# mSD-Shield_v10.net
KiCad netlist of a schematic drawn in EAGLE
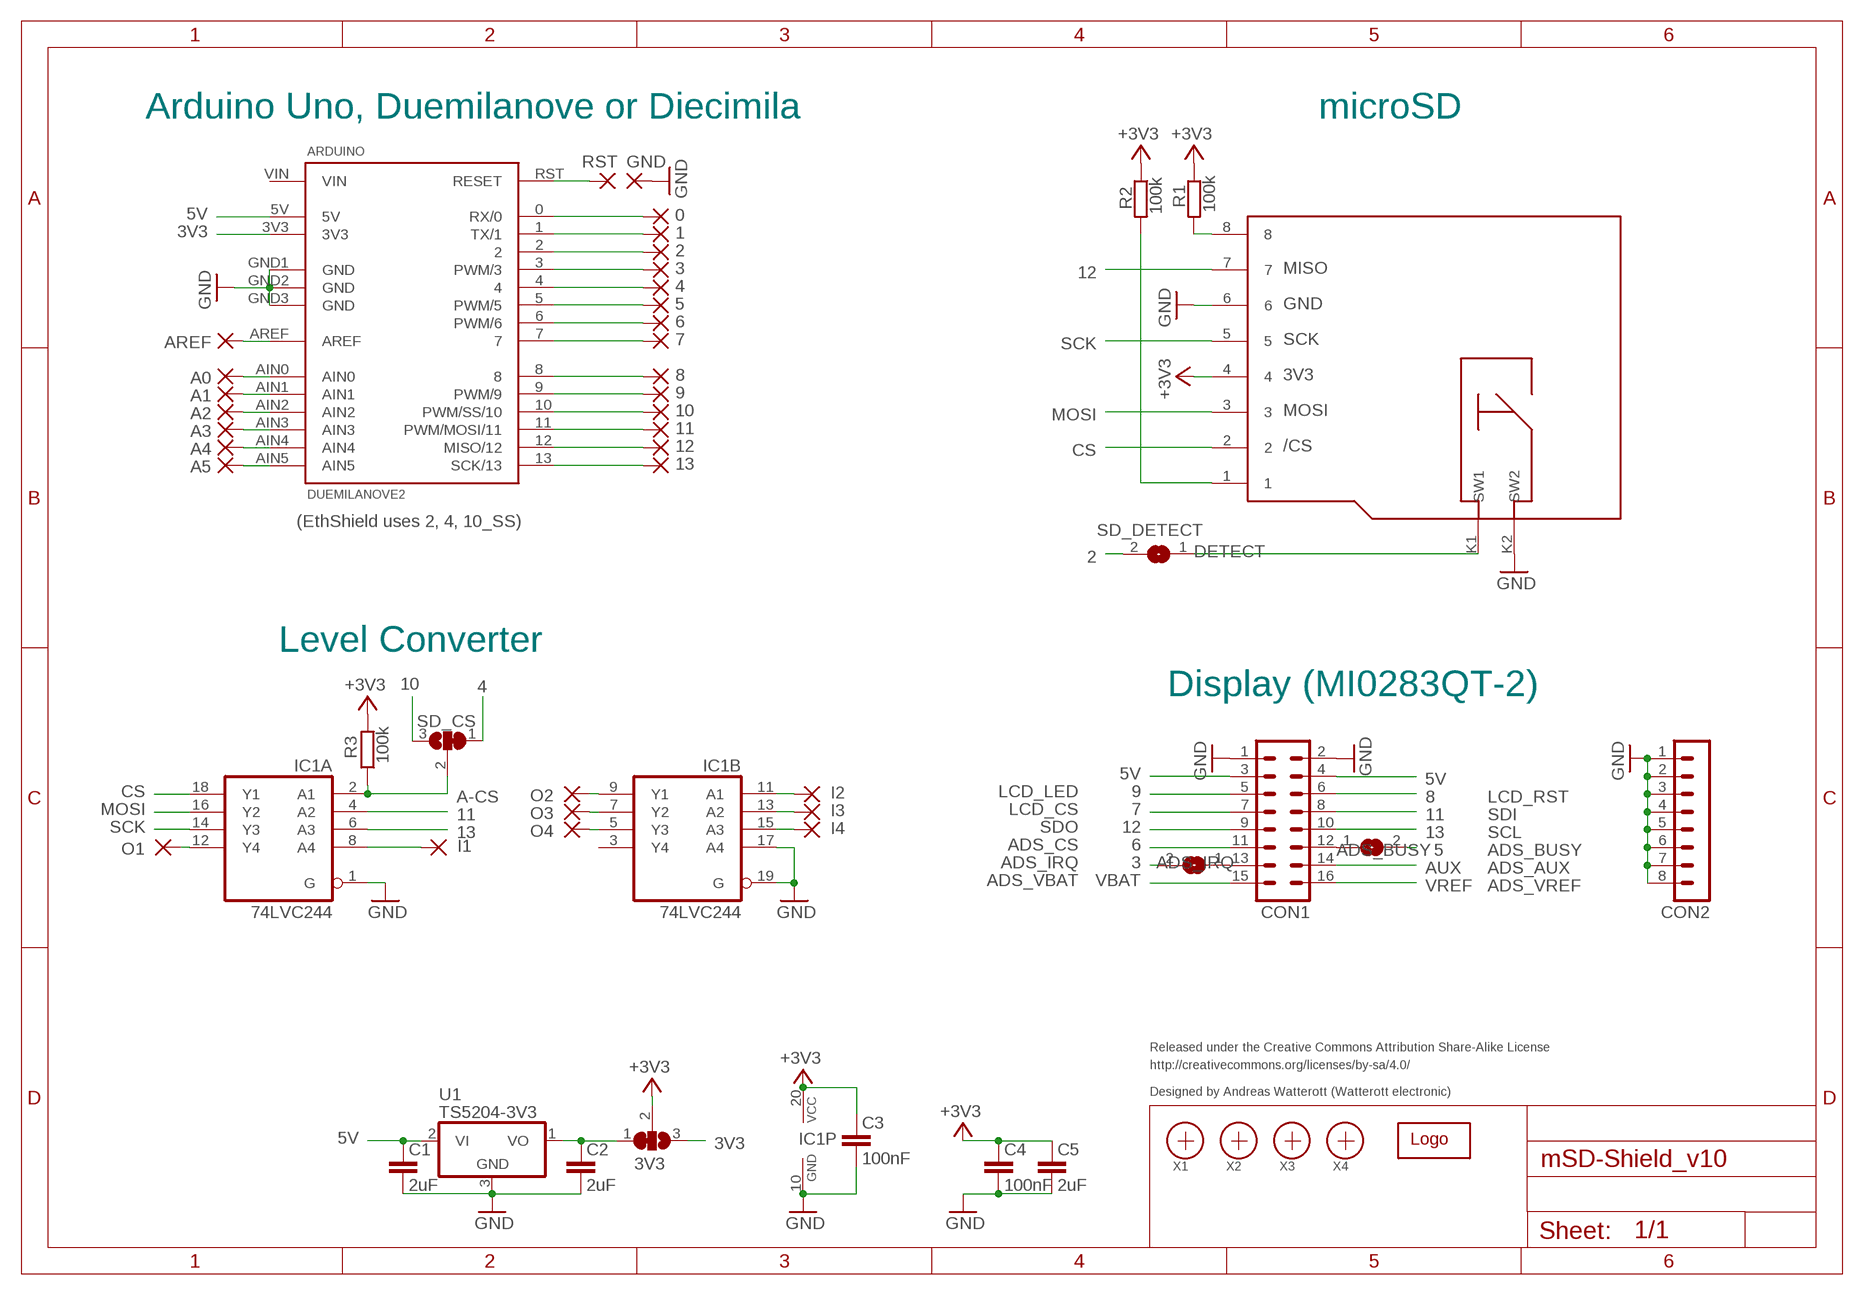
[diagram p0: schematic, sheet 1]

(export (version "E")
  (design (tool "Eeschema 10.0.6"))
  (components
    (comp (ref "0")
      (value "1,6/0,8")
      (footprint "eagle-import:1,6_0,8")
      (libsource (lib "eagle-import") (part "1,6/0,8"))
    )
    (comp (ref "1")
      (value "1,6/0,8")
      (footprint "eagle-import:1,6_0,8")
      (libsource (lib "eagle-import") (part "1,6/0,8"))
    )
    (comp (ref "2")
      (value "1,6/0,8")
      (footprint "eagle-import:1,6_0,8")
      (libsource (lib "eagle-import") (part "1,6/0,8"))
    )
    (comp (ref "3")
      (value "1,6/0,8")
      (footprint "eagle-import:1,6_0,8")
      (libsource (lib "eagle-import") (part "1,6/0,8"))
    )
    (comp (ref "3V3")
      (value "SJ2W")
      (footprint "eagle-import:SJ_2")
      (libsource (lib "eagle-import") (part "SJ2W"))
    )
    (comp (ref "4")
      (value "1,6/0,8")
      (footprint "eagle-import:1,6_0,8")
      (libsource (lib "eagle-import") (part "1,6/0,8"))
    )
    (comp (ref "5")
      (value "1,6/0,8")
      (footprint "eagle-import:1,6_0,8")
      (libsource (lib "eagle-import") (part "1,6/0,8"))
    )
    (comp (ref "6")
      (value "1,6/0,8")
      (footprint "eagle-import:1,6_0,8")
      (libsource (lib "eagle-import") (part "1,6/0,8"))
    )
    (comp (ref "7")
      (value "1,6/0,8")
      (footprint "eagle-import:1,6_0,8")
      (libsource (lib "eagle-import") (part "1,6/0,8"))
    )
    (comp (ref "8")
      (value "1,6/0,8")
      (footprint "eagle-import:1,6_0,8")
      (libsource (lib "eagle-import") (part "1,6/0,8"))
    )
    (comp (ref "9")
      (value "1,6/0,8")
      (footprint "eagle-import:1,6_0,8")
      (libsource (lib "eagle-import") (part "1,6/0,8"))
    )
    (comp (ref "10")
      (value "1,6/0,8")
      (footprint "eagle-import:1,6_0,8")
      (libsource (lib "eagle-import") (part "1,6/0,8"))
    )
    (comp (ref "11")
      (value "1,6/0,8")
      (footprint "eagle-import:1,6_0,8")
      (libsource (lib "eagle-import") (part "1,6/0,8"))
    )
    (comp (ref "12")
      (value "1,6/0,8")
      (footprint "eagle-import:1,6_0,8")
      (libsource (lib "eagle-import") (part "1,6/0,8"))
    )
    (comp (ref "13")
      (value "1,6/0,8")
      (footprint "eagle-import:1,6_0,8")
      (libsource (lib "eagle-import") (part "1,6/0,8"))
    )
    (comp (ref "A0")
      (value "1,6/0,8")
      (footprint "eagle-import:1,6_0,8")
      (libsource (lib "eagle-import") (part "1,6/0,8"))
    )
    (comp (ref "A1")
      (value "1,6/0,8")
      (footprint "eagle-import:1,6_0,8")
      (libsource (lib "eagle-import") (part "1,6/0,8"))
    )
    (comp (ref "A2")
      (value "1,6/0,8")
      (footprint "eagle-import:1,6_0,8")
      (libsource (lib "eagle-import") (part "1,6/0,8"))
    )
    (comp (ref "A3")
      (value "1,6/0,8")
      (footprint "eagle-import:1,6_0,8")
      (libsource (lib "eagle-import") (part "1,6/0,8"))
    )
    (comp (ref "A4")
      (value "1,6/0,8")
      (footprint "eagle-import:1,6_0,8")
      (libsource (lib "eagle-import") (part "1,6/0,8"))
    )
    (comp (ref "A5")
      (value "1,6/0,8")
      (footprint "eagle-import:1,6_0,8")
      (libsource (lib "eagle-import") (part "1,6/0,8"))
    )
    (comp (ref "ADS_BUSY")
      (value "SJ")
      (footprint "eagle-import:SJ")
      (libsource (lib "eagle-import") (part "SJ"))
    )
    (comp (ref "ADS_IRQ")
      (value "SJ")
      (footprint "eagle-import:SJ")
      (libsource (lib "eagle-import") (part "SJ"))
    )
    (comp (ref "ARDUINO")
      (value "DUEMILANOVE2")
      (footprint "eagle-import:DUEMILANOVE2")
      (libsource (lib "eagle-import") (part "DUEMILANOVE2"))
    )
    (comp (ref "AREF")
      (value "1,6/0,8")
      (footprint "eagle-import:1,6_0,8")
      (libsource (lib "eagle-import") (part "1,6/0,8"))
    )
    (comp (ref "C1")
      (value "2uF")
      (footprint "eagle-import:C0805")
      (libsource (lib "eagle-import") (part "C-EUC0805"))
    )
    (comp (ref "C2")
      (value "2uF")
      (footprint "eagle-import:C0805")
      (libsource (lib "eagle-import") (part "C-EUC0805"))
    )
    (comp (ref "C3")
      (value "100nF")
      (footprint "eagle-import:C0603")
      (libsource (lib "eagle-import") (part "C-EUC0603"))
    )
    (comp (ref "C4")
      (value "100nF")
      (footprint "eagle-import:C0603")
      (libsource (lib "eagle-import") (part "C-EUC0603"))
    )
    (comp (ref "C5")
      (value "2uF")
      (footprint "eagle-import:C0603")
      (libsource (lib "eagle-import") (part "C-EUC0603"))
    )
    (comp (ref "CON1")
      (value "MA08-2")
      (footprint "eagle-import:MA08-2")
      (libsource (lib "eagle-import") (part "MA08-2"))
    )
    (comp (ref "CON2")
      (value "MA08-1")
      (footprint "eagle-import:MA08-1")
      (libsource (lib "eagle-import") (part "MA08-1"))
    )
    (comp (ref "GND")
      (value "SMD2")
      (footprint "eagle-import:SMD1,27-2,54")
      (libsource (lib "eagle-import") (part "SMD2"))
    )
    (comp (ref "I1")
      (value "SMD2")
      (footprint "eagle-import:SMD1,27-2,54")
      (libsource (lib "eagle-import") (part "SMD2"))
    )
    (comp (ref "I2")
      (value "SMD2")
      (footprint "eagle-import:SMD1,27-2,54")
      (libsource (lib "eagle-import") (part "SMD2"))
    )
    (comp (ref "I3")
      (value "SMD2")
      (footprint "eagle-import:SMD1,27-2,54")
      (libsource (lib "eagle-import") (part "SMD2"))
    )
    (comp (ref "I4")
      (value "SMD2")
      (footprint "eagle-import:SMD1,27-2,54")
      (libsource (lib "eagle-import") (part "SMD2"))
    )
    (comp (ref "IC1")
      (value "74LVC244")
      (footprint "eagle-import:SO20W")
      (libsource (lib "eagle-import") (part "74244DWHC"))
    )
    (comp (ref "O1")
      (value "SMD2")
      (footprint "eagle-import:SMD1,27-2,54")
      (libsource (lib "eagle-import") (part "SMD2"))
    )
    (comp (ref "O2")
      (value "SMD2")
      (footprint "eagle-import:SMD1,27-2,54")
      (libsource (lib "eagle-import") (part "SMD2"))
    )
    (comp (ref "O3")
      (value "SMD2")
      (footprint "eagle-import:SMD1,27-2,54")
      (libsource (lib "eagle-import") (part "SMD2"))
    )
    (comp (ref "O4")
      (value "SMD2")
      (footprint "eagle-import:SMD1,27-2,54")
      (libsource (lib "eagle-import") (part "SMD2"))
    )
    (comp (ref "R1")
      (value "100k")
      (footprint "eagle-import:R0603")
      (libsource (lib "eagle-import") (part "R-EU_R0603"))
    )
    (comp (ref "R2")
      (value "100k")
      (footprint "eagle-import:R0603")
      (libsource (lib "eagle-import") (part "R-EU_R0603"))
    )
    (comp (ref "R3")
      (value "100k")
      (footprint "eagle-import:R0603")
      (libsource (lib "eagle-import") (part "R-EU_R0603"))
    )
    (comp (ref "RST")
      (value "SMD2")
      (footprint "eagle-import:SMD1,27-2,54")
      (libsource (lib "eagle-import") (part "SMD2"))
    )
    (comp (ref "SD_CS")
      (value "SJ2W")
      (footprint "eagle-import:SJ_2")
      (libsource (lib "eagle-import") (part "SJ2W"))
    )
    (comp (ref "SD_DETECT")
      (value "SJ")
      (footprint "eagle-import:SJ")
      (libsource (lib "eagle-import") (part "SJ"))
    )
    (comp (ref "U$1")
      (value "WE-LOGO")
      (footprint "eagle-import:WE-LOGO")
      (libsource (lib "eagle-import") (part "WE-LOGO"))
    )
    (comp (ref "U1")
      (value "TS5204-3V3")
      (footprint "eagle-import:SOT23")
      (libsource (lib "eagle-import") (part "TS5204"))
    )
    (comp (ref "X1")
      (value "PASSER")
      (footprint "eagle-import:PASSER")
      (libsource (lib "eagle-import") (part "PASSER"))
    )
    (comp (ref "X2")
      (value "PASSER")
      (footprint "eagle-import:PASSER")
      (libsource (lib "eagle-import") (part "PASSER"))
    )
    (comp (ref "X3")
      (value "PASSER")
      (footprint "eagle-import:PASSER")
      (libsource (lib "eagle-import") (part "PASSER"))
    )
    (comp (ref "X4")
      (value "PASSER")
      (footprint "eagle-import:PASSER")
      (libsource (lib "eagle-import") (part "PASSER"))
    )
    (comp (ref "X5")
      (value "MICRO-SD")
      (footprint "eagle-import:MICRO-SD")
      (libsource (lib "eagle-import") (part "MICRO-SD"))
    )
  )
  (nets
    (net (code "1") (name "+3V3") (class "Default")
      (node (ref "3V3") (pin "2") (pinfunction "2_2") (pintype "passive"))
      (node (ref "C3") (pin "1") (pinfunction "1_1") (pintype "passive"))
      (node (ref "C4") (pin "1") (pinfunction "1_1") (pintype "passive"))
      (node (ref "C5") (pin "1") (pinfunction "1_1") (pintype "passive"))
      (node (ref "IC1") (pin "20") (pinfunction "VCC_20") (pintype "power_in"))
      (node (ref "R1") (pin "1") (pinfunction "1_1") (pintype "passive"))
      (node (ref "R2") (pin "1") (pinfunction "1_1") (pintype "passive"))
      (node (ref "R3") (pin "2") (pinfunction "2_2") (pintype "passive"))
      (node (ref "X5") (pin "4") (pinfunction "4_4") (pintype "bidirectional"))
    )
    (net (code "2") (name "/2") (class "Default")
      (node (ref "2") (pin "1") (pinfunction "P_1") (pintype "passive"))
      (node (ref "ARDUINO") (pin "2") (pinfunction "2_2") (pintype "bidirectional"))
      (node (ref "SD_DETECT") (pin "2") (pinfunction "2_2") (pintype "passive"))
    )
    (net (code "3") (name "/3") (class "Default")
      (node (ref "3") (pin "1") (pinfunction "P_1") (pintype "passive"))
      (node (ref "ADS_IRQ") (pin "2") (pinfunction "2_2") (pintype "passive"))
      (node (ref "ARDUINO") (pin "3") (pinfunction "PWM/3_3") (pintype "bidirectional"))
    )
    (net (code "4") (name "/3V3") (class "Default")
      (node (ref "3V3") (pin "3") (pinfunction "3_3") (pintype "passive"))
      (node (ref "ARDUINO") (pin "3V3") (pinfunction "3V3_3V3") (pintype "power_in"))
    )
    (net (code "5") (name "/4") (class "Default")
      (node (ref "4") (pin "1") (pinfunction "P_1") (pintype "passive"))
      (node (ref "ARDUINO") (pin "4") (pinfunction "4_4") (pintype "bidirectional"))
      (node (ref "SD_CS") (pin "1") (pinfunction "1_1") (pintype "passive"))
    )
    (net (code "6") (name "/5") (class "Default")
      (node (ref "5") (pin "1") (pinfunction "P_1") (pintype "passive"))
      (node (ref "ADS_BUSY") (pin "2") (pinfunction "2_2") (pintype "passive"))
      (node (ref "ARDUINO") (pin "5") (pinfunction "PWM/5_5") (pintype "bidirectional"))
    )
    (net (code "7") (name "/5V") (class "Default")
      (node (ref "ARDUINO") (pin "5V") (pinfunction "5V_5V") (pintype "power_in"))
      (node (ref "C1") (pin "1") (pinfunction "1_1") (pintype "passive"))
      (node (ref "CON1") (pin "3") (pinfunction "3_3") (pintype "passive"))
      (node (ref "CON1") (pin "4") (pinfunction "4_4") (pintype "passive"))
      (node (ref "U1") (pin "2") (pinfunction "VI_2") (pintype "input"))
    )
    (net (code "8") (name "/6") (class "Default")
      (node (ref "6") (pin "1") (pinfunction "P_1") (pintype "passive"))
      (node (ref "ARDUINO") (pin "6") (pinfunction "PWM/6_6") (pintype "bidirectional"))
      (node (ref "CON1") (pin "11") (pinfunction "11_11") (pintype "passive"))
    )
    (net (code "9") (name "/7") (class "Default")
      (node (ref "7") (pin "1") (pinfunction "P_1") (pintype "passive"))
      (node (ref "ARDUINO") (pin "7") (pinfunction "7_7") (pintype "bidirectional"))
      (node (ref "CON1") (pin "7") (pinfunction "7_7") (pintype "passive"))
    )
    (net (code "10") (name "/8") (class "Default")
      (node (ref "8") (pin "1") (pinfunction "P_1") (pintype "passive"))
      (node (ref "ARDUINO") (pin "8") (pinfunction "8_8") (pintype "bidirectional"))
      (node (ref "CON1") (pin "6") (pinfunction "6_6") (pintype "passive"))
    )
    (net (code "11") (name "/9") (class "Default")
      (node (ref "9") (pin "1") (pinfunction "P_1") (pintype "passive"))
      (node (ref "ARDUINO") (pin "9") (pinfunction "PWM/9_9") (pintype "bidirectional"))
      (node (ref "CON1") (pin "5") (pinfunction "5_5") (pintype "passive"))
    )
    (net (code "12") (name "/10") (class "Default")
      (node (ref "10") (pin "1") (pinfunction "P_1") (pintype "passive"))
      (node (ref "ARDUINO") (pin "10") (pinfunction "PWM/SS/10_10") (pintype "bidirectional"))
      (node (ref "SD_CS") (pin "3") (pinfunction "3_3") (pintype "passive"))
    )
    (net (code "13") (name "/11") (class "Default")
      (node (ref "11") (pin "1") (pinfunction "P_1") (pintype "passive"))
      (node (ref "ARDUINO") (pin "11") (pinfunction "PWM/MOSI/11_11") (pintype "bidirectional"))
      (node (ref "CON1") (pin "8") (pinfunction "8_8") (pintype "passive"))
      (node (ref "IC1") (pin "4") (pinfunction "A2_4") (pintype "input"))
    )
    (net (code "14") (name "/12") (class "Default")
      (node (ref "12") (pin "1") (pinfunction "P_1") (pintype "passive"))
      (node (ref "ARDUINO") (pin "12") (pinfunction "MISO/12_12") (pintype "bidirectional"))
      (node (ref "CON1") (pin "9") (pinfunction "9_9") (pintype "passive"))
      (node (ref "X5") (pin "7") (pinfunction "7_7") (pintype "bidirectional"))
    )
    (net (code "15") (name "/13") (class "Default")
      (node (ref "13") (pin "1") (pinfunction "P_1") (pintype "passive"))
      (node (ref "ARDUINO") (pin "13") (pinfunction "SCK/13_13") (pintype "bidirectional"))
      (node (ref "CON1") (pin "10") (pinfunction "10_10") (pintype "passive"))
      (node (ref "IC1") (pin "6") (pinfunction "A3_6") (pintype "input"))
    )
    (net (code "16") (name "/A-CS") (class "Default")
      (node (ref "IC1") (pin "2") (pinfunction "A1_2") (pintype "input"))
      (node (ref "R3") (pin "1") (pinfunction "1_1") (pintype "passive"))
      (node (ref "SD_CS") (pin "2") (pinfunction "2_2") (pintype "passive"))
    )
    (net (code "17") (name "/AUX") (class "Default")
      (node (ref "CON1") (pin "14") (pinfunction "14_14") (pintype "passive"))
    )
    (net (code "18") (name "/CS") (class "Default")
      (node (ref "IC1") (pin "18") (pinfunction "Y1_18") (pintype "tri_state"))
      (node (ref "X5") (pin "2") (pinfunction "2_2") (pintype "bidirectional"))
    )
    (net (code "19") (name "/DETECT") (class "Default")
      (node (ref "SD_DETECT") (pin "1") (pinfunction "1_1") (pintype "passive"))
      (node (ref "X5") (pin "K1") (pinfunction "SW1_K1") (pintype "bidirectional"))
    )
    (net (code "20") (name "/MOSI") (class "Default")
      (node (ref "IC1") (pin "16") (pinfunction "Y2_16") (pintype "tri_state"))
      (node (ref "X5") (pin "3") (pinfunction "3_3") (pintype "bidirectional"))
    )
    (net (code "21") (name "/SCK") (class "Default")
      (node (ref "IC1") (pin "14") (pinfunction "Y3_14") (pintype "tri_state"))
      (node (ref "X5") (pin "5") (pinfunction "5_5") (pintype "bidirectional"))
    )
    (net (code "22") (name "/VBAT") (class "Default")
      (node (ref "CON1") (pin "15") (pinfunction "15_15") (pintype "passive"))
    )
    (net (code "23") (name "/VIN") (class "Default")
      (node (ref "ARDUINO") (pin "VIN") (pinfunction "VIN_VIN") (pintype "power_in"))
    )
    (net (code "24") (name "/VREF") (class "Default")
      (node (ref "CON1") (pin "16") (pinfunction "16_16") (pintype "passive"))
    )
    (net (code "25") (name "GND") (class "Default")
      (node (ref "ARDUINO") (pin "GND1") (pinfunction "GND_GND1") (pintype "power_in"))
      (node (ref "ARDUINO") (pin "GND2") (pinfunction "GND_GND2") (pintype "power_in"))
      (node (ref "ARDUINO") (pin "GND3") (pinfunction "GND_GND3") (pintype "power_in"))
      (node (ref "C1") (pin "2") (pinfunction "2_2") (pintype "passive"))
      (node (ref "C2") (pin "2") (pinfunction "2_2") (pintype "passive"))
      (node (ref "C3") (pin "2") (pinfunction "2_2") (pintype "passive"))
      (node (ref "C4") (pin "2") (pinfunction "2_2") (pintype "passive"))
      (node (ref "C5") (pin "2") (pinfunction "2_2") (pintype "passive"))
      (node (ref "CON1") (pin "1") (pinfunction "1_1") (pintype "passive"))
      (node (ref "CON1") (pin "2") (pinfunction "2_2") (pintype "passive"))
      (node (ref "CON2") (pin "1") (pinfunction "1_1") (pintype "passive"))
      (node (ref "CON2") (pin "2") (pinfunction "2_2") (pintype "passive"))
      (node (ref "CON2") (pin "3") (pinfunction "3_3") (pintype "passive"))
      (node (ref "CON2") (pin "4") (pinfunction "4_4") (pintype "passive"))
      (node (ref "CON2") (pin "5") (pinfunction "5_5") (pintype "passive"))
      (node (ref "CON2") (pin "6") (pinfunction "6_6") (pintype "passive"))
      (node (ref "CON2") (pin "7") (pinfunction "7_7") (pintype "passive"))
      (node (ref "CON2") (pin "8") (pinfunction "8_8") (pintype "passive"))
      (node (ref "GND") (pin "1") (pinfunction "P_1") (pintype "passive"))
      (node (ref "IC1") (pin "1") (pinfunction "G_1") (pintype "input"))
      (node (ref "IC1") (pin "10") (pinfunction "GND_10") (pintype "power_in"))
      (node (ref "IC1") (pin "17") (pinfunction "A4_17") (pintype "input"))
      (node (ref "IC1") (pin "19") (pinfunction "G_19") (pintype "input"))
      (node (ref "U1") (pin "3") (pinfunction "GND_3") (pintype "passive"))
      (node (ref "X5") (pin "6") (pinfunction "6_6") (pintype "bidirectional"))
      (node (ref "X5") (pin "K2") (pinfunction "SW2_K2") (pintype "bidirectional"))
    )
    (net (code "26") (name "Net-(0-P)") (class "Default")
      (node (ref "0") (pin "1") (pinfunction "P_1") (pintype "passive"))
      (node (ref "ARDUINO") (pin "0") (pinfunction "RX/0_0") (pintype "bidirectional"))
    )
    (net (code "27") (name "Net-(1-P)") (class "Default")
      (node (ref "1") (pin "1") (pinfunction "P_1") (pintype "passive"))
      (node (ref "ARDUINO") (pin "1") (pinfunction "TX/1_1") (pintype "bidirectional"))
    )
    (net (code "28") (name "Net-(A0-P)") (class "Default")
      (node (ref "A0") (pin "1") (pinfunction "P_1") (pintype "passive"))
      (node (ref "ARDUINO") (pin "AIN0") (pinfunction "AIN0_AIN0") (pintype "bidirectional"))
    )
    (net (code "29") (name "Net-(A1-P)") (class "Default")
      (node (ref "A1") (pin "1") (pinfunction "P_1") (pintype "passive"))
      (node (ref "ARDUINO") (pin "AIN1") (pinfunction "AIN1_AIN1") (pintype "bidirectional"))
    )
    (net (code "30") (name "Net-(A2-P)") (class "Default")
      (node (ref "A2") (pin "1") (pinfunction "P_1") (pintype "passive"))
      (node (ref "ARDUINO") (pin "AIN2") (pinfunction "AIN2_AIN2") (pintype "bidirectional"))
    )
    (net (code "31") (name "Net-(A3-P)") (class "Default")
      (node (ref "A3") (pin "1") (pinfunction "P_1") (pintype "passive"))
      (node (ref "ARDUINO") (pin "AIN3") (pinfunction "AIN3_AIN3") (pintype "bidirectional"))
    )
    (net (code "32") (name "Net-(A4-P)") (class "Default")
      (node (ref "A4") (pin "1") (pinfunction "P_1") (pintype "passive"))
      (node (ref "ARDUINO") (pin "AIN4") (pinfunction "AIN4_AIN4") (pintype "bidirectional"))
    )
    (net (code "33") (name "Net-(A5-P)") (class "Default")
      (node (ref "A5") (pin "1") (pinfunction "P_1") (pintype "passive"))
      (node (ref "ARDUINO") (pin "AIN5") (pinfunction "AIN5_AIN5") (pintype "bidirectional"))
    )
    (net (code "34") (name "Net-(ADS_BUSY-Pad1)") (class "Default")
      (node (ref "ADS_BUSY") (pin "1") (pinfunction "1_1") (pintype "passive"))
      (node (ref "CON1") (pin "12") (pinfunction "12_12") (pintype "passive"))
    )
    (net (code "35") (name "Net-(ADS_IRQ-Pad1)") (class "Default")
      (node (ref "ADS_IRQ") (pin "1") (pinfunction "1_1") (pintype "passive"))
      (node (ref "CON1") (pin "13") (pinfunction "13_13") (pintype "passive"))
    )
    (net (code "36") (name "Net-(ARDUINO-RESET)") (class "Default")
      (node (ref "ARDUINO") (pin "RST") (pinfunction "RESET_RST") (pintype "bidirectional"))
      (node (ref "RST") (pin "1") (pinfunction "P_1") (pintype "passive"))
    )
    (net (code "37") (name "Net-(AREF-P)") (class "Default")
      (node (ref "ARDUINO") (pin "AREF") (pinfunction "AREF_AREF") (pintype "power_in"))
      (node (ref "AREF") (pin "1") (pinfunction "P_1") (pintype "passive"))
    )
    (net (code "38") (name "Net-(I1-P)") (class "Default")
      (node (ref "I1") (pin "1") (pinfunction "P_1") (pintype "passive"))
      (node (ref "IC1") (pin "8") (pinfunction "A4_8") (pintype "input"))
    )
    (net (code "39") (name "Net-(I2-P)") (class "Default")
      (node (ref "I2") (pin "1") (pinfunction "P_1") (pintype "passive"))
      (node (ref "IC1") (pin "11") (pinfunction "A1_11") (pintype "input"))
    )
    (net (code "40") (name "Net-(I3-P)") (class "Default")
      (node (ref "I3") (pin "1") (pinfunction "P_1") (pintype "passive"))
      (node (ref "IC1") (pin "13") (pinfunction "A2_13") (pintype "input"))
    )
    (net (code "41") (name "Net-(I4-P)") (class "Default")
      (node (ref "I4") (pin "1") (pinfunction "P_1") (pintype "passive"))
      (node (ref "IC1") (pin "15") (pinfunction "A3_15") (pintype "input"))
    )
    (net (code "42") (name "Net-(IC1A-Y4)") (class "Default")
      (node (ref "IC1") (pin "12") (pinfunction "Y4_12") (pintype "tri_state"))
      (node (ref "O1") (pin "1") (pinfunction "P_1") (pintype "passive"))
    )
    (net (code "43") (name "Net-(IC1B-Y1)") (class "Default")
      (node (ref "IC1") (pin "9") (pinfunction "Y1_9") (pintype "tri_state"))
      (node (ref "O2") (pin "1") (pinfunction "P_1") (pintype "passive"))
    )
    (net (code "44") (name "Net-(IC1B-Y2)") (class "Default")
      (node (ref "IC1") (pin "7") (pinfunction "Y2_7") (pintype "tri_state"))
      (node (ref "O3") (pin "1") (pinfunction "P_1") (pintype "passive"))
    )
    (net (code "45") (name "Net-(IC1B-Y3)") (class "Default")
      (node (ref "IC1") (pin "5") (pinfunction "Y3_5") (pintype "tri_state"))
      (node (ref "O4") (pin "1") (pinfunction "P_1") (pintype "passive"))
    )
    (net (code "46") (name "Net-(R1-Pad2)") (class "Default")
      (node (ref "R1") (pin "2") (pinfunction "2_2") (pintype "passive"))
      (node (ref "X5") (pin "8") (pinfunction "8_8") (pintype "bidirectional"))
    )
    (net (code "47") (name "Net-(R2-Pad2)") (class "Default")
      (node (ref "R2") (pin "2") (pinfunction "2_2") (pintype "passive"))
      (node (ref "X5") (pin "1") (pinfunction "1_1") (pintype "bidirectional"))
    )
    (net (code "48") (name "Net-(U1-VO)") (class "Default")
      (node (ref "3V3") (pin "1") (pinfunction "1_1") (pintype "passive"))
      (node (ref "C2") (pin "1") (pinfunction "1_1") (pintype "passive"))
      (node (ref "U1") (pin "1") (pinfunction "VO_1") (pintype "passive"))
    )
    (net (code "49") (name "unconnected-(IC1B-Y4-Pad3)") (class "Default")
      (node (ref "IC1") (pin "3") (pinfunction "Y4_3") (pintype "tri_state"))
    )
  )
)
